# Contactos.net
KiCad netlist of a schematic drawn in Altium Designer
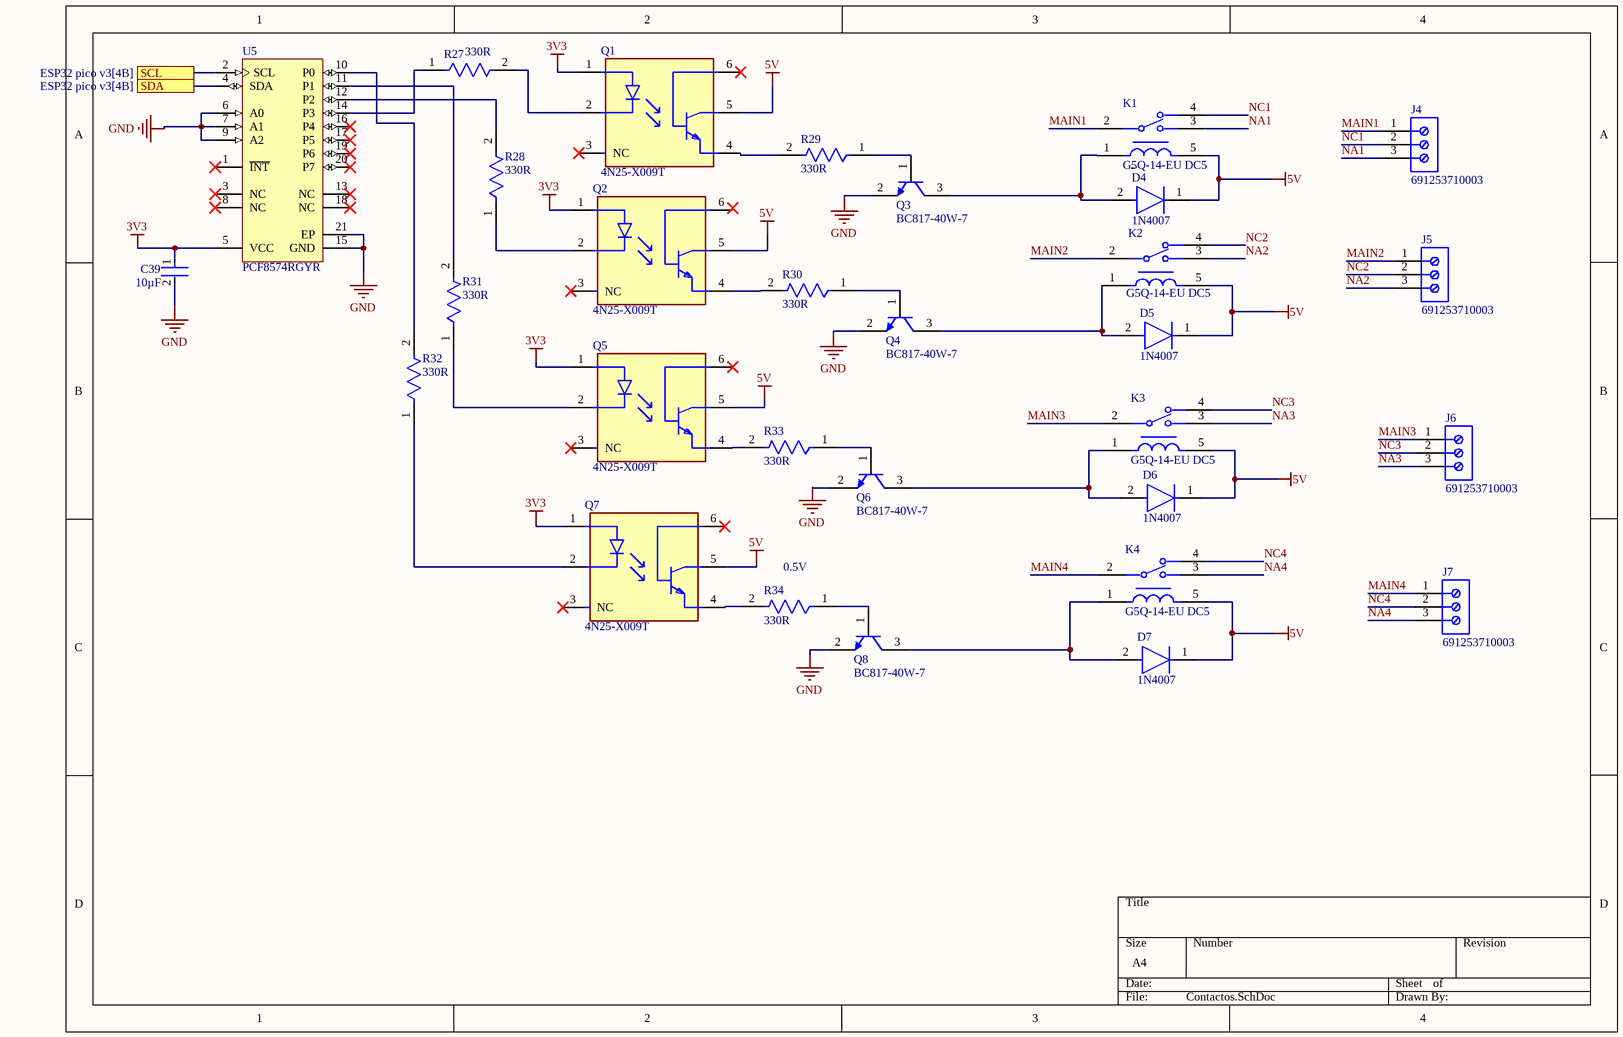
[diagram p0: Contactos.SchDoc]

(export (version "E")
  (design (tool "Eeschema 10.0.6"))
  (components
    (comp (ref "C39")
      (value "CC0603KRX5R7BB106")
      (footprint "FP-CC0603-DC-MFG")
      (description "CC0603KRX5R7BB106 Multilayer Ceramic Capacitor, 10 uF, 16 V, ± 10%, X5R, 0603 [1608 Metric]")
      (fields (field (name "CAPACITANCE") "10µF") (field (name "TOLERANCE") "10%"))
      (libsource (lib "Altium Content Vault") (part "b4654b650e69147ec39a6b967a45e02"))
    )
    (comp (ref "D4")
      (value "1N4007")
      (footprint "FP-1N4007-MFG")
      (description "Rectifier diode 1000 V 1 A DO-41, ,")
      (fields
        (field (name "MANUFACTURER") "Diotec")
        (field (name "OCTOPART") "https://octopart.com/1n4007-diotec-4040411")
      )
      (libsource (lib "Altium Content Vault") (part "d7152d700b627762746794eb795d46e"))
    )
    (comp (ref "D5")
      (value "1N4007")
      (footprint "FP-1N4007-MFG")
      (description "Rectifier diode 1000 V 1 A DO-41, ,")
      (fields
        (field (name "MANUFACTURER") "Diotec")
        (field (name "OCTOPART") "https://octopart.com/1n4007-diotec-4040411")
      )
      (libsource (lib "Altium Content Vault") (part "d7152d700b627762746794eb795d46e"))
    )
    (comp (ref "D6")
      (value "1N4007")
      (footprint "FP-1N4007-MFG")
      (description "Rectifier diode 1000 V 1 A DO-41, ,")
      (fields
        (field (name "MANUFACTURER") "Diotec")
        (field (name "OCTOPART") "https://octopart.com/1n4007-diotec-4040411")
      )
      (libsource (lib "Altium Content Vault") (part "d7152d700b627762746794eb795d46e"))
    )
    (comp (ref "D7")
      (value "1N4007")
      (footprint "FP-1N4007-MFG")
      (description "Rectifier diode 1000 V 1 A DO-41, ,")
      (fields
        (field (name "MANUFACTURER") "Diotec")
        (field (name "OCTOPART") "https://octopart.com/1n4007-diotec-4040411")
      )
      (libsource (lib "Altium Content Vault") (part "d7152d700b627762746794eb795d46e"))
    )
    (comp (ref "J4")
      (value "691253710003")
      (footprint "691253710003")
      (description "Terminal Block, 5.08MM Pitch, Horizontal, Modular, Rising Cage Clamp, 3PINS")
      (libsource (lib "") (part "TBL - 1R - 03P - Screw_2"))
    )
    (comp (ref "J5")
      (value "691253710003")
      (footprint "691253710003")
      (description "Terminal Block, 5.08MM Pitch, Horizontal, Modular, Rising Cage Clamp, 3PINS")
      (libsource (lib "") (part "TBL - 1R - 03P - Screw_1"))
    )
    (comp (ref "J6")
      (value "691253710003")
      (footprint "691253710003")
      (description "Terminal Block, 5.08MM Pitch, Horizontal, Modular, Rising Cage Clamp, 3PINS")
      (libsource (lib "Altium Content Vault") (part "TBL - 1R - 03P - Screw"))
    )
    (comp (ref "J7")
      (value "691253710003")
      (footprint "691253710003")
      (description "Terminal Block, 5.08MM Pitch, Horizontal, Modular, Rising Cage Clamp, 3PINS")
      (libsource (lib "Altium Content Vault") (part "TBL - 1R - 03P - Screw"))
    )
    (comp (ref "K1")
      (value "G5Q-14-EU DC5")
      (footprint "FP-G5Q-14-EU_DC5-MFG")
      (description "RELAY GEN PURPOSE SPDT 10A 5V")
      (libsource (lib "Altium Content Vault") (part "09d7468cc7bd4f4e7a2ff62bdae3adb"))
    )
    (comp (ref "K2")
      (value "G5Q-14-EU DC5")
      (footprint "FP-G5Q-14-EU_DC5-MFG")
      (description "RELAY GEN PURPOSE SPDT 10A 5V")
      (libsource (lib "Altium Content Vault") (part "09d7468cc7bd4f4e7a2ff62bdae3adb"))
    )
    (comp (ref "K3")
      (value "G5Q-14-EU DC5")
      (footprint "FP-G5Q-14-EU_DC5-MFG")
      (description "RELAY GEN PURPOSE SPDT 10A 5V")
      (libsource (lib "Altium Content Vault") (part "09d7468cc7bd4f4e7a2ff62bdae3adb"))
    )
    (comp (ref "K4")
      (value "G5Q-14-EU DC5")
      (footprint "FP-G5Q-14-EU_DC5-MFG")
      (description "RELAY GEN PURPOSE SPDT 10A 5V")
      (libsource (lib "Altium Content Vault") (part "09d7468cc7bd4f4e7a2ff62bdae3adb"))
    )
    (comp (ref "Q1")
      (value "4N25-X009T")
      (footprint "FP-4N25-X009T-MFG")
      (description "4N25-X009T Optocoupler DC-IN 1-CH Transistor With Base DC-OUT 6-Pin PDIP SMD T/R")
      (libsource (lib "Altium Content Vault") (part "cc3cd645612a37f745648d5741cac6e"))
    )
    (comp (ref "Q2")
      (value "4N25-X009T")
      (footprint "FP-4N25-X009T-MFG")
      (description "4N25-X009T Optocoupler DC-IN 1-CH Transistor With Base DC-OUT 6-Pin PDIP SMD T/R")
      (libsource (lib "Altium Content Vault") (part "cc3cd645612a37f745648d5741cac6e"))
    )
    (comp (ref "Q3")
      (value "BC817-40W-7")
      (footprint "DIOD-SOT323-3_V")
      (description "NPN Small Signal Transistor, 45 V, 500 mA, -65 to 150 degC, 3-Pin SOT323, RoHS, Tape and Reel")
      (fields (field (name "MANUFACTURER") "DiodesIncorporated"))
      (libsource (lib "Altium Content Vault") (part "BJT-NPN-BEC-3"))
    )
    (comp (ref "Q4")
      (value "BC817-40W-7")
      (footprint "DIOD-SOT323-3_V")
      (description "NPN Small Signal Transistor, 45 V, 500 mA, -65 to 150 degC, 3-Pin SOT323, RoHS, Tape and Reel")
      (fields (field (name "MANUFACTURER") "DiodesIncorporated"))
      (libsource (lib "Altium Content Vault") (part "BJT-NPN-BEC-3"))
    )
    (comp (ref "Q5")
      (value "4N25-X009T")
      (footprint "FP-4N25-X009T-MFG")
      (description "4N25-X009T Optocoupler DC-IN 1-CH Transistor With Base DC-OUT 6-Pin PDIP SMD T/R")
      (libsource (lib "Altium Content Vault") (part "cc3cd645612a37f745648d5741cac6e"))
    )
    (comp (ref "Q6")
      (value "BC817-40W-7")
      (footprint "DIOD-SOT323-3_V")
      (description "NPN Small Signal Transistor, 45 V, 500 mA, -65 to 150 degC, 3-Pin SOT323, RoHS, Tape and Reel")
      (fields (field (name "MANUFACTURER") "DiodesIncorporated"))
      (libsource (lib "Altium Content Vault") (part "BJT-NPN-BEC-3"))
    )
    (comp (ref "Q7")
      (value "4N25-X009T")
      (footprint "FP-4N25-X009T-MFG")
      (description "4N25-X009T Optocoupler DC-IN 1-CH Transistor With Base DC-OUT 6-Pin PDIP SMD T/R")
      (libsource (lib "Altium Content Vault") (part "cc3cd645612a37f745648d5741cac6e"))
    )
    (comp (ref "Q8")
      (value "BC817-40W-7")
      (footprint "DIOD-SOT323-3_V")
      (description "NPN Small Signal Transistor, 45 V, 500 mA, -65 to 150 degC, 3-Pin SOT323, RoHS, Tape and Reel")
      (fields (field (name "MANUFACTURER") "DiodesIncorporated"))
      (libsource (lib "Altium Content Vault") (part "BJT-NPN-BEC-3"))
    )
    (comp (ref "R27")
      (value "CRCW0603330RFKEA")
      (footprint "FP-CRCW0603-e3-MFG")
      (description "RES Thick Film, 330Ω, 1%, 0.1W, 100ppm/°C, 0603")
      (fields (field (name "TOLERANCE") "1%") (field (name "RESISTANCE") "330R"))
      (libsource (lib "Altium Content Vault") (part "1029c3af85768c4190bb7ad29bc67b5"))
    )
    (comp (ref "R28")
      (value "CRCW0603330RFKEA")
      (footprint "FP-CRCW0603-e3-MFG")
      (description "RES Thick Film, 330Ω, 1%, 0.1W, 100ppm/°C, 0603")
      (fields (field (name "TOLERANCE") "1%") (field (name "RESISTANCE") "330R"))
      (libsource (lib "Altium Content Vault") (part "1029c3af85768c4190bb7ad29bc67b5"))
    )
    (comp (ref "R29")
      (value "CRCW0603330RFKEA")
      (footprint "FP-CRCW0603-e3-MFG")
      (description "RES Thick Film, 330Ω, 1%, 0.1W, 100ppm/°C, 0603")
      (fields (field (name "TOLERANCE") "1%") (field (name "RESISTANCE") "330R"))
      (libsource (lib "Altium Content Vault") (part "1029c3af85768c4190bb7ad29bc67b5"))
    )
    (comp (ref "R30")
      (value "CRCW0603330RFKEA")
      (footprint "FP-CRCW0603-e3-MFG")
      (description "RES Thick Film, 330Ω, 1%, 0.1W, 100ppm/°C, 0603")
      (fields (field (name "TOLERANCE") "1%") (field (name "RESISTANCE") "330R"))
      (libsource (lib "Altium Content Vault") (part "1029c3af85768c4190bb7ad29bc67b5"))
    )
    (comp (ref "R31")
      (value "CRCW0603330RFKEA")
      (footprint "FP-CRCW0603-e3-MFG")
      (description "RES Thick Film, 330Ω, 1%, 0.1W, 100ppm/°C, 0603")
      (fields (field (name "TOLERANCE") "1%") (field (name "RESISTANCE") "330R"))
      (libsource (lib "Altium Content Vault") (part "1029c3af85768c4190bb7ad29bc67b5"))
    )
    (comp (ref "R32")
      (value "CRCW0603330RFKEA")
      (footprint "FP-CRCW0603-e3-MFG")
      (description "RES Thick Film, 330Ω, 1%, 0.1W, 100ppm/°C, 0603")
      (fields (field (name "TOLERANCE") "1%") (field (name "RESISTANCE") "330R"))
      (libsource (lib "Altium Content Vault") (part "1029c3af85768c4190bb7ad29bc67b5"))
    )
    (comp (ref "R33")
      (value "CRCW0603330RFKEA")
      (footprint "FP-CRCW0603-e3-MFG")
      (description "RES Thick Film, 330Ω, 1%, 0.1W, 100ppm/°C, 0603")
      (fields (field (name "TOLERANCE") "1%") (field (name "RESISTANCE") "330R"))
      (libsource (lib "Altium Content Vault") (part "1029c3af85768c4190bb7ad29bc67b5"))
    )
    (comp (ref "R34")
      (value "CRCW0603330RFKEA")
      (footprint "FP-CRCW0603-e3-MFG")
      (description "RES Thick Film, 330Ω, 1%, 0.1W, 100ppm/°C, 0603")
      (fields (field (name "TOLERANCE") "1%") (field (name "RESISTANCE") "330R"))
      (libsource (lib "Altium Content Vault") (part "1029c3af85768c4190bb7ad29bc67b5"))
    )
    (comp (ref "U5")
      (value "PCF8574RGYR")
      (footprint "RGY0020A_V")
      (fields (field (name "MANUFACTURER") "Texas Instruments"))
      (libsource (lib "Altium Content Vault") (part "TI-PCF8574-VQFN_RGY-20"))
    )
  )
  (nets
    (net (code "1") (name "/MAIN1") (class "Default")
      (node (ref "J4") (pin "1") (pinfunction "1_1") (pintype "passive"))
      (node (ref "K1") (pin "2") (pinfunction "2_2") (pintype "passive"))
    )
    (net (code "2") (name "/MAIN2") (class "Default")
      (node (ref "J5") (pin "1") (pinfunction "1_1") (pintype "passive"))
      (node (ref "K2") (pin "2") (pinfunction "2_2") (pintype "passive"))
    )
    (net (code "3") (name "/MAIN3") (class "Default")
      (node (ref "J6") (pin "1") (pinfunction "1_1") (pintype "passive"))
      (node (ref "K3") (pin "2") (pinfunction "2_2") (pintype "passive"))
    )
    (net (code "4") (name "/MAIN4") (class "Default")
      (node (ref "J7") (pin "1") (pinfunction "1_1") (pintype "passive"))
      (node (ref "K4") (pin "2") (pinfunction "2_2") (pintype "passive"))
    )
    (net (code "5") (name "/NA1") (class "Default")
      (node (ref "J4") (pin "3") (pinfunction "3_3") (pintype "passive"))
      (node (ref "K1") (pin "3") (pinfunction "3_3") (pintype "passive"))
    )
    (net (code "6") (name "/NA2") (class "Default")
      (node (ref "J5") (pin "3") (pinfunction "3_3") (pintype "passive"))
      (node (ref "K2") (pin "3") (pinfunction "3_3") (pintype "passive"))
    )
    (net (code "7") (name "/NA3") (class "Default")
      (node (ref "J6") (pin "3") (pinfunction "3_3") (pintype "passive"))
      (node (ref "K3") (pin "3") (pinfunction "3_3") (pintype "passive"))
    )
    (net (code "8") (name "/NA4") (class "Default")
      (node (ref "J7") (pin "3") (pinfunction "3_3") (pintype "passive"))
      (node (ref "K4") (pin "3") (pinfunction "3_3") (pintype "passive"))
    )
    (net (code "9") (name "/NC1") (class "Default")
      (node (ref "J4") (pin "2") (pinfunction "2_2") (pintype "passive"))
      (node (ref "K1") (pin "4") (pinfunction "4_4") (pintype "passive"))
    )
    (net (code "10") (name "/NC2") (class "Default")
      (node (ref "J5") (pin "2") (pinfunction "2_2") (pintype "passive"))
      (node (ref "K2") (pin "4") (pinfunction "4_4") (pintype "passive"))
    )
    (net (code "11") (name "/NC3") (class "Default")
      (node (ref "J6") (pin "2") (pinfunction "2_2") (pintype "passive"))
      (node (ref "K3") (pin "4") (pinfunction "4_4") (pintype "passive"))
    )
    (net (code "12") (name "/NC4") (class "Default")
      (node (ref "J7") (pin "2") (pinfunction "2_2") (pintype "passive"))
      (node (ref "K4") (pin "4") (pinfunction "4_4") (pintype "passive"))
    )
    (net (code "13") (name "/SCL") (class "Default")
      (node (ref "U5") (pin "2") (pinfunction "SCL_2") (pintype "input"))
    )
    (net (code "14") (name "/SDA") (class "Default")
      (node (ref "U5") (pin "4") (pinfunction "SDA_4") (pintype "bidirectional"))
    )
    (net (code "15") (name "3V3") (class "Default")
      (node (ref "C39") (pin "1") (pinfunction "1_1") (pintype "passive"))
      (node (ref "Q1") (pin "1") (pinfunction "A_1") (pintype "passive"))
      (node (ref "Q2") (pin "1") (pinfunction "A_1") (pintype "passive"))
      (node (ref "Q5") (pin "1") (pinfunction "A_1") (pintype "passive"))
      (node (ref "Q7") (pin "1") (pinfunction "A_1") (pintype "passive"))
      (node (ref "U5") (pin "5") (pinfunction "VCC_5") (pintype "power_in"))
    )
    (net (code "16") (name "5V") (class "Default")
      (node (ref "D4") (pin "1") (pinfunction "C_1") (pintype "passive"))
      (node (ref "D5") (pin "1") (pinfunction "C_1") (pintype "passive"))
      (node (ref "D6") (pin "1") (pinfunction "C_1") (pintype "passive"))
      (node (ref "D7") (pin "1") (pinfunction "C_1") (pintype "passive"))
      (node (ref "K1") (pin "5") (pinfunction "5_5") (pintype "passive"))
      (node (ref "K2") (pin "5") (pinfunction "5_5") (pintype "passive"))
      (node (ref "K3") (pin "5") (pinfunction "5_5") (pintype "passive"))
      (node (ref "K4") (pin "5") (pinfunction "5_5") (pintype "passive"))
      (node (ref "Q1") (pin "5") (pinfunction "C_5") (pintype "passive"))
      (node (ref "Q2") (pin "5") (pinfunction "C_5") (pintype "passive"))
      (node (ref "Q5") (pin "5") (pinfunction "C_5") (pintype "passive"))
      (node (ref "Q7") (pin "5") (pinfunction "C_5") (pintype "passive"))
    )
    (net (code "17") (name "GND") (class "Default")
      (node (ref "C39") (pin "2") (pinfunction "2_2") (pintype "passive"))
      (node (ref "Q3") (pin "2") (pinfunction "E_2") (pintype "passive"))
      (node (ref "Q4") (pin "2") (pinfunction "E_2") (pintype "passive"))
      (node (ref "Q6") (pin "2") (pinfunction "E_2") (pintype "passive"))
      (node (ref "Q8") (pin "2") (pinfunction "E_2") (pintype "passive"))
      (node (ref "U5") (pin "15") (pinfunction "GND_15") (pintype "power_in"))
      (node (ref "U5") (pin "21") (pinfunction "EP_21") (pintype "passive"))
      (node (ref "U5") (pin "6") (pinfunction "A0_6") (pintype "input"))
      (node (ref "U5") (pin "7") (pinfunction "A1_7") (pintype "input"))
      (node (ref "U5") (pin "9") (pinfunction "A2_9") (pintype "input"))
    )
    (net (code "18") (name "Net-(D4-A)") (class "Default")
      (node (ref "D4") (pin "2") (pinfunction "A_2") (pintype "passive"))
      (node (ref "K1") (pin "1") (pinfunction "1_1") (pintype "passive"))
      (node (ref "Q3") (pin "3") (pinfunction "C_3") (pintype "passive"))
    )
    (net (code "19") (name "Net-(D5-A)") (class "Default")
      (node (ref "D5") (pin "2") (pinfunction "A_2") (pintype "passive"))
      (node (ref "K2") (pin "1") (pinfunction "1_1") (pintype "passive"))
      (node (ref "Q4") (pin "3") (pinfunction "C_3") (pintype "passive"))
    )
    (net (code "20") (name "Net-(D6-A)") (class "Default")
      (node (ref "D6") (pin "2") (pinfunction "A_2") (pintype "passive"))
      (node (ref "K3") (pin "1") (pinfunction "1_1") (pintype "passive"))
      (node (ref "Q6") (pin "3") (pinfunction "C_3") (pintype "passive"))
    )
    (net (code "21") (name "Net-(D7-A)") (class "Default")
      (node (ref "D7") (pin "2") (pinfunction "A_2") (pintype "passive"))
      (node (ref "K4") (pin "1") (pinfunction "1_1") (pintype "passive"))
      (node (ref "Q8") (pin "3") (pinfunction "C_3") (pintype "passive"))
    )
    (net (code "22") (name "Net-(Q1-C-Pad2)") (class "Default")
      (node (ref "Q1") (pin "2") (pinfunction "C_2") (pintype "passive"))
      (node (ref "R27") (pin "2") (pinfunction "2_2") (pintype "passive"))
    )
    (net (code "23") (name "Net-(Q1-E)") (class "Default")
      (node (ref "Q1") (pin "4") (pinfunction "E_4") (pintype "passive"))
      (node (ref "R29") (pin "2") (pinfunction "2_2") (pintype "passive"))
    )
    (net (code "24") (name "Net-(Q2-C-Pad2)") (class "Default")
      (node (ref "Q2") (pin "2") (pinfunction "C_2") (pintype "passive"))
      (node (ref "R28") (pin "1") (pinfunction "1_1") (pintype "passive"))
    )
    (net (code "25") (name "Net-(Q2-E)") (class "Default")
      (node (ref "Q2") (pin "4") (pinfunction "E_4") (pintype "passive"))
      (node (ref "R30") (pin "2") (pinfunction "2_2") (pintype "passive"))
    )
    (net (code "26") (name "Net-(Q3-B)") (class "Default")
      (node (ref "Q3") (pin "1") (pinfunction "B_1") (pintype "passive"))
      (node (ref "R29") (pin "1") (pinfunction "1_1") (pintype "passive"))
    )
    (net (code "27") (name "Net-(Q4-B)") (class "Default")
      (node (ref "Q4") (pin "1") (pinfunction "B_1") (pintype "passive"))
      (node (ref "R30") (pin "1") (pinfunction "1_1") (pintype "passive"))
    )
    (net (code "28") (name "Net-(Q5-C-Pad2)") (class "Default")
      (node (ref "Q5") (pin "2") (pinfunction "C_2") (pintype "passive"))
      (node (ref "R31") (pin "1") (pinfunction "1_1") (pintype "passive"))
    )
    (net (code "29") (name "Net-(Q5-E)") (class "Default")
      (node (ref "Q5") (pin "4") (pinfunction "E_4") (pintype "passive"))
      (node (ref "R33") (pin "2") (pinfunction "2_2") (pintype "passive"))
    )
    (net (code "30") (name "Net-(Q6-B)") (class "Default")
      (node (ref "Q6") (pin "1") (pinfunction "B_1") (pintype "passive"))
      (node (ref "R33") (pin "1") (pinfunction "1_1") (pintype "passive"))
    )
    (net (code "31") (name "Net-(Q7-C-Pad2)") (class "Default")
      (node (ref "Q7") (pin "2") (pinfunction "C_2") (pintype "passive"))
      (node (ref "R32") (pin "1") (pinfunction "1_1") (pintype "passive"))
    )
    (net (code "32") (name "Net-(Q7-E)") (class "Default")
      (node (ref "Q7") (pin "4") (pinfunction "E_4") (pintype "passive"))
      (node (ref "R34") (pin "2") (pinfunction "2_2") (pintype "passive"))
    )
    (net (code "33") (name "Net-(Q8-B)") (class "Default")
      (node (ref "Q8") (pin "1") (pinfunction "B_1") (pintype "passive"))
      (node (ref "R34") (pin "1") (pinfunction "1_1") (pintype "passive"))
    )
    (net (code "34") (name "Net-(U5-P0)") (class "Default")
      (node (ref "R32") (pin "2") (pinfunction "2_2") (pintype "passive"))
      (node (ref "U5") (pin "10") (pinfunction "P0_10") (pintype "bidirectional"))
    )
    (net (code "35") (name "Net-(U5-P1)") (class "Default")
      (node (ref "R31") (pin "2") (pinfunction "2_2") (pintype "passive"))
      (node (ref "U5") (pin "11") (pinfunction "P1_11") (pintype "bidirectional"))
    )
    (net (code "36") (name "Net-(U5-P2)") (class "Default")
      (node (ref "R28") (pin "2") (pinfunction "2_2") (pintype "passive"))
      (node (ref "U5") (pin "12") (pinfunction "P2_12") (pintype "bidirectional"))
    )
    (net (code "37") (name "Net-(U5-P3)") (class "Default")
      (node (ref "R27") (pin "1") (pinfunction "1_1") (pintype "passive"))
      (node (ref "U5") (pin "14") (pinfunction "P3_14") (pintype "bidirectional"))
    )
    (net (code "38") (name "unconnected-(Q1-B-Pad6)") (class "Default")
      (node (ref "Q1") (pin "6") (pinfunction "B_6") (pintype "passive+no_connect"))
    )
    (net (code "39") (name "unconnected-(Q1-NC-Pad3)") (class "Default")
      (node (ref "Q1") (pin "3") (pinfunction "NC_3") (pintype "passive+no_connect"))
    )
    (net (code "40") (name "unconnected-(Q2-B-Pad6)") (class "Default")
      (node (ref "Q2") (pin "6") (pinfunction "B_6") (pintype "passive"))
    )
    (net (code "41") (name "unconnected-(Q2-NC-Pad3)") (class "Default")
      (node (ref "Q2") (pin "3") (pinfunction "NC_3") (pintype "passive+no_connect"))
    )
    (net (code "42") (name "unconnected-(Q5-B-Pad6)") (class "Default")
      (node (ref "Q5") (pin "6") (pinfunction "B_6") (pintype "passive+no_connect"))
    )
    (net (code "43") (name "unconnected-(Q5-NC-Pad3)") (class "Default")
      (node (ref "Q5") (pin "3") (pinfunction "NC_3") (pintype "passive+no_connect"))
    )
    (net (code "44") (name "unconnected-(Q7-B-Pad6)") (class "Default")
      (node (ref "Q7") (pin "6") (pinfunction "B_6") (pintype "passive+no_connect"))
    )
    (net (code "45") (name "unconnected-(Q7-NC-Pad3)") (class "Default")
      (node (ref "Q7") (pin "3") (pinfunction "NC_3") (pintype "passive+no_connect"))
    )
    (net (code "46") (name "unconnected-(U5-NC-Pad3)") (class "Default")
      (node (ref "U5") (pin "3") (pinfunction "NC_3") (pintype "passive+no_connect"))
    )
    (net (code "47") (name "unconnected-(U5-NC-Pad8)") (class "Default")
      (node (ref "U5") (pin "8") (pinfunction "NC_8") (pintype "passive+no_connect"))
    )
    (net (code "48") (name "unconnected-(U5-NC-Pad13)") (class "Default")
      (node (ref "U5") (pin "13") (pinfunction "NC_13") (pintype "passive+no_connect"))
    )
    (net (code "49") (name "unconnected-(U5-NC-Pad18)") (class "Default")
      (node (ref "U5") (pin "18") (pinfunction "NC_18") (pintype "passive+no_connect"))
    )
    (net (code "50") (name "unconnected-(U5-P4-Pad16)") (class "Default")
      (node (ref "U5") (pin "16") (pinfunction "P4_16") (pintype "bidirectional+no_connect"))
    )
    (net (code "51") (name "unconnected-(U5-P5-Pad17)") (class "Default")
      (node (ref "U5") (pin "17") (pinfunction "P5_17") (pintype "bidirectional+no_connect"))
    )
    (net (code "52") (name "unconnected-(U5-P6-Pad19)") (class "Default")
      (node (ref "U5") (pin "19") (pinfunction "P6_19") (pintype "bidirectional+no_connect"))
    )
    (net (code "53") (name "unconnected-(U5-P7-Pad20)") (class "Default")
      (node (ref "U5") (pin "20") (pinfunction "P7_20") (pintype "bidirectional+no_connect"))
    )
    (net (code "54") (name "unconnected-(U5-~{INT}-Pad1)") (class "Default")
      (node (ref "U5") (pin "1") (pinfunction "~{INT}_1") (pintype "open_collector+no_connect"))
    )
  )
)
